# MiniBee.net
KiCad netlist of a schematic drawn in EAGLE
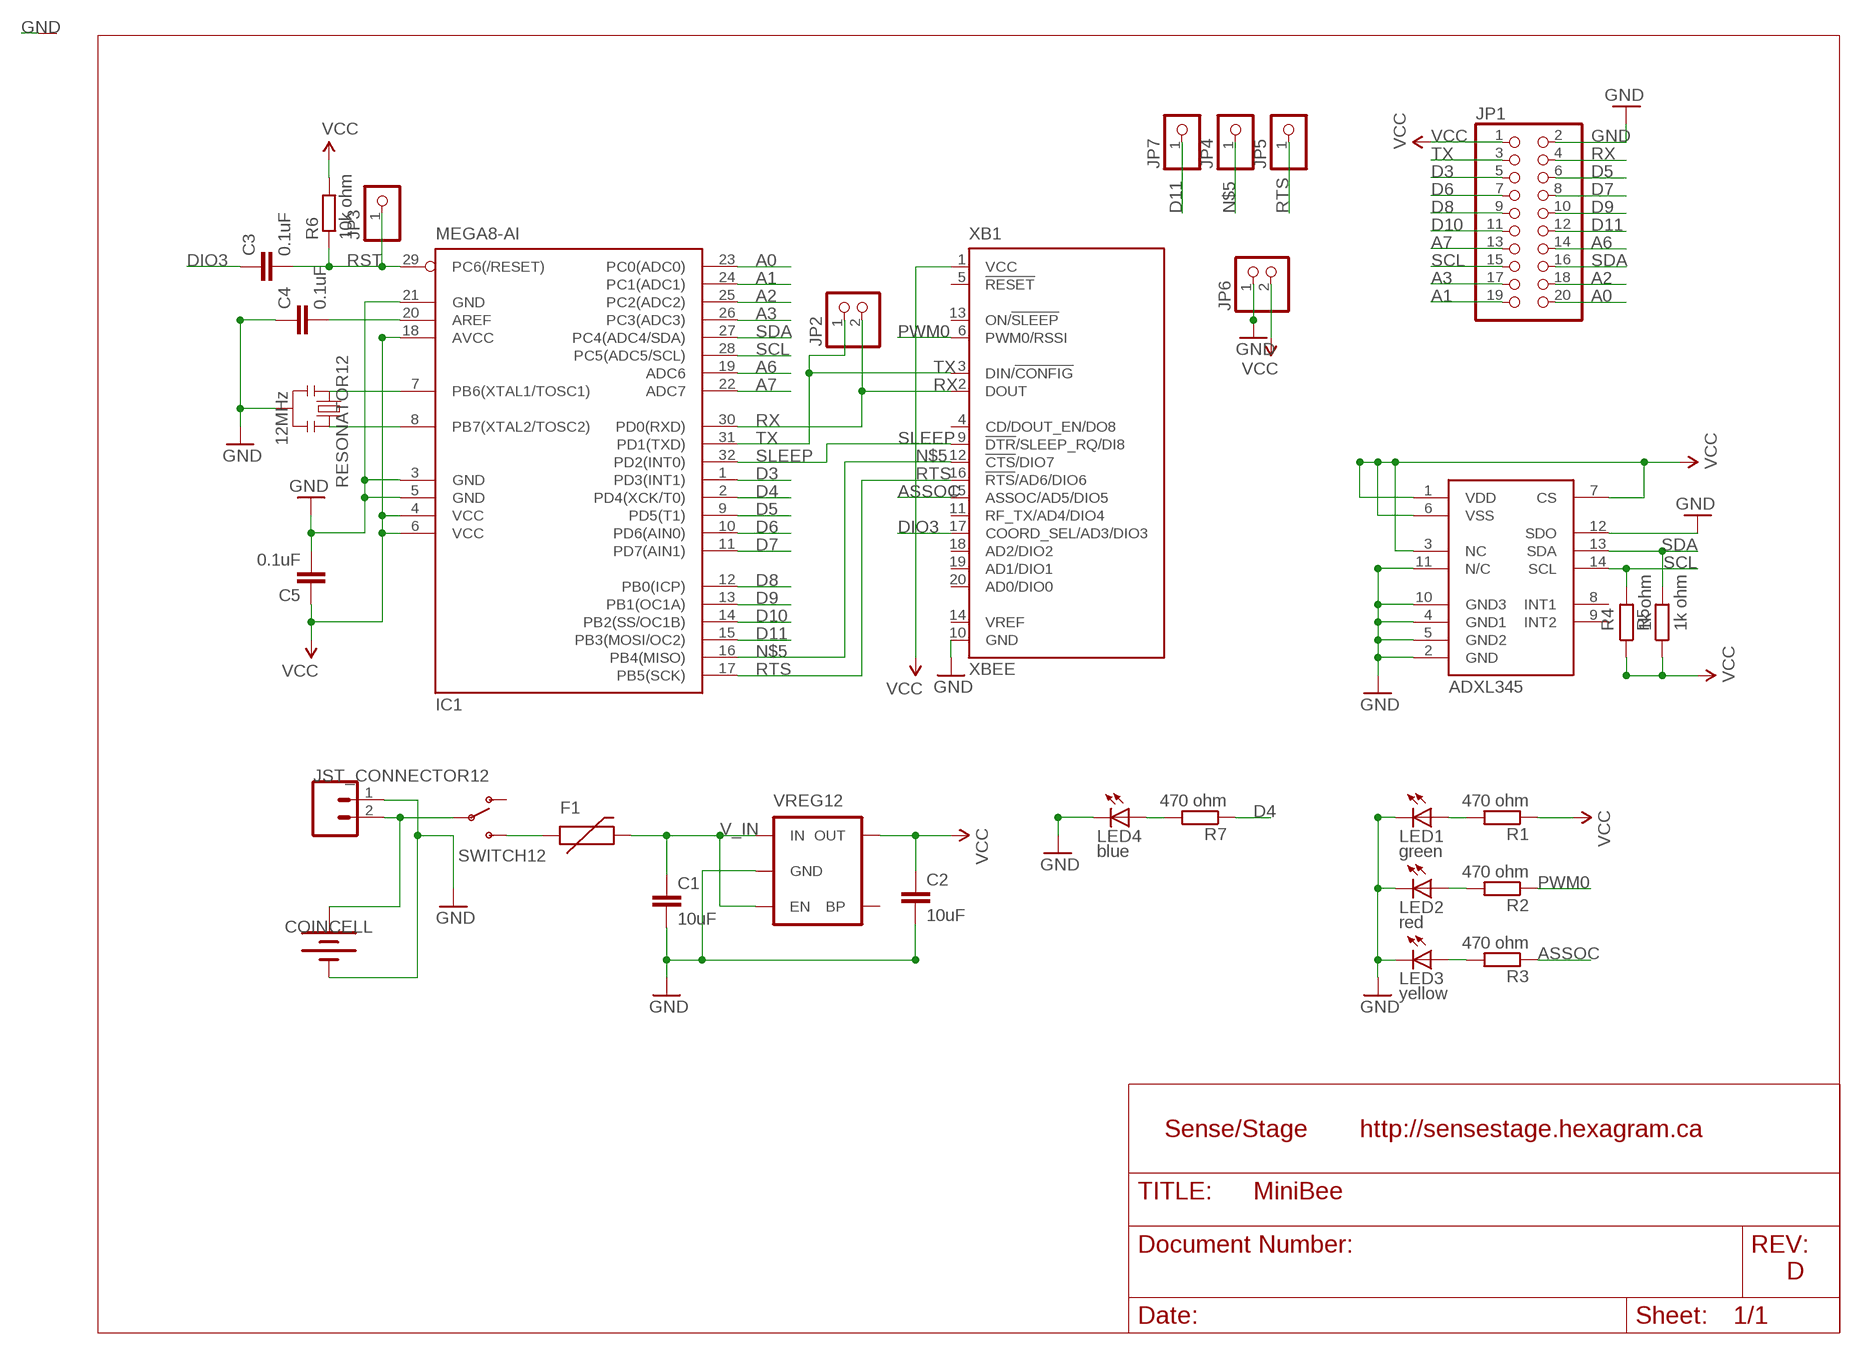
[diagram p0: schematic, sheet 1]

(export (version "E")
  (design (tool "Eeschema 10.0.6"))
  (components
    (comp (ref "C1")
      (value "10uF")
      (footprint "eagle-import:C0805")
      (libsource (lib "eagle-import") (part "C-EUC0805"))
    )
    (comp (ref "C2")
      (value "10uF")
      (footprint "eagle-import:C0805")
      (libsource (lib "eagle-import") (part "C-EUC0805"))
    )
    (comp (ref "C3")
      (value "0.1uF")
      (footprint "eagle-import:C0402")
      (libsource (lib "eagle-import") (part "C-EUC0402"))
    )
    (comp (ref "C4")
      (value "0.1uF")
      (footprint "eagle-import:C0402")
      (libsource (lib "eagle-import") (part "C-EUC0402"))
    )
    (comp (ref "C5")
      (value "0.1uF")
      (footprint "eagle-import:C0402K")
      (libsource (lib "eagle-import") (part "C-EUC0402K"))
    )
    (comp (ref "COINCELL12")
      (value "COINCELL")
      (footprint "eagle-import:KEYSTONE_BATTERY_HOLDER")
      (libsource (lib "eagle-import") (part "KEYSTONE_BATTERY_HOLDER"))
    )
    (comp (ref "F1")
      (value "PTCSMD")
      (footprint "eagle-import:PTC-1206")
      (libsource (lib "eagle-import") (part "PTCSMD"))
    )
    (comp (ref "IC1")
      (value "MEGA8-AI")
      (footprint "eagle-import:TQFP32-08")
      (fields (field (name "MPN") "ATMEGA8-16AU"))
      (libsource (lib "eagle-import") (part "MEGA8-AI"))
    )
    (comp (ref "JP1")
      (value "PINHD-2X10")
      (footprint "eagle-import:2X10")
      (libsource (lib "eagle-import") (part "PINHD-2X10"))
    )
    (comp (ref "JP2")
      (value "PINHD-1X2")
      (footprint "eagle-import:1X02")
      (libsource (lib "eagle-import") (part "PINHD-1X2"))
    )
    (comp (ref "JP3")
      (value "PINHD-1X1")
      (footprint "eagle-import:1X01")
      (libsource (lib "eagle-import") (part "PINHD-1X1"))
    )
    (comp (ref "JP4")
      (value "PINHD-1X1")
      (footprint "eagle-import:1X01")
      (libsource (lib "eagle-import") (part "PINHD-1X1"))
    )
    (comp (ref "JP5")
      (value "PINHD-1X1")
      (footprint "eagle-import:1X01")
      (libsource (lib "eagle-import") (part "PINHD-1X1"))
    )
    (comp (ref "JP6")
      (value "PINHD-1X2")
      (footprint "eagle-import:1X02")
      (libsource (lib "eagle-import") (part "PINHD-1X2"))
    )
    (comp (ref "JP7")
      (value "PINHD-1X1")
      (footprint "eagle-import:1X01")
      (libsource (lib "eagle-import") (part "PINHD-1X1"))
    )
    (comp (ref "JST_CONNECTOR12")
      (value "JST_CONNECTOR")
      (footprint "eagle-import:S2B-PH")
      (libsource (lib "eagle-import") (part "M02-JST-2MM-SMT"))
    )
    (comp (ref "LED1")
      (value "green")
      (footprint "eagle-import:CHIP-LED0603")
      (libsource (lib "eagle-import") (part "LEDCHIP-LED0603"))
    )
    (comp (ref "LED2")
      (value "red")
      (footprint "eagle-import:CHIP-LED0603")
      (libsource (lib "eagle-import") (part "LEDCHIP-LED0603"))
    )
    (comp (ref "LED3")
      (value "yellow")
      (footprint "eagle-import:CHIP-LED0603")
      (libsource (lib "eagle-import") (part "LEDCHIP-LED0603"))
    )
    (comp (ref "LED4")
      (value "blue")
      (footprint "eagle-import:CHIP-LED0603")
      (libsource (lib "eagle-import") (part "LEDCHIP-LED0603"))
    )
    (comp (ref "R1")
      (value "470 ohm")
      (footprint "eagle-import:R0402")
      (libsource (lib "eagle-import") (part "R-EU_R0402"))
    )
    (comp (ref "R2")
      (value "470 ohm")
      (footprint "eagle-import:R0402")
      (libsource (lib "eagle-import") (part "R-EU_R0402"))
    )
    (comp (ref "R3")
      (value "470 ohm")
      (footprint "eagle-import:R0402")
      (libsource (lib "eagle-import") (part "R-EU_R0402"))
    )
    (comp (ref "R4")
      (value "1k ohm")
      (footprint "eagle-import:R0402")
      (libsource (lib "eagle-import") (part "R-EU_R0402"))
    )
    (comp (ref "R5")
      (value "1k ohm")
      (footprint "eagle-import:R0402")
      (libsource (lib "eagle-import") (part "R-EU_R0402"))
    )
    (comp (ref "R6")
      (value "10k ohm")
      (footprint "eagle-import:R0402")
      (libsource (lib "eagle-import") (part "R-EU_R0402"))
    )
    (comp (ref "R7")
      (value "470 ohm")
      (footprint "eagle-import:R0402")
      (libsource (lib "eagle-import") (part "R-EU_R0402"))
    )
    (comp (ref "RESONATOR12")
      (value "12MHz")
      (footprint "eagle-import:RESONATOR-SMD")
      (libsource (lib "eagle-import") (part "RESONATORSMD"))
    )
    (comp (ref "SWITCH12")
      (value "MYSHIT_PCM_SWITCH")
      (footprint "eagle-import:MYSHIT_PCM_SWITCH_RA")
      (libsource (lib "eagle-import") (part "MYSHIT_PCM_SWITCH"))
    )
    (comp (ref "U1")
      (value "ADXL345")
      (footprint "eagle-import:LGA14")
      (libsource (lib "eagle-import") (part "ADXL345"))
    )
    (comp (ref "VP_0")
      (value "VPDEV0")
      (footprint "eagle-import:VPAC0")
      (libsource (lib "eagle-import") (part "VPDEV0"))
    )
    (comp (ref "VREG12")
      (value "V_REG_LDOSMD")
      (footprint "eagle-import:SOT23-5")
      (libsource (lib "eagle-import") (part "V_REG_LDOSMD"))
    )
    (comp (ref "XB1")
      (value "XBEE")
      (footprint "eagle-import:XBEE")
      (fields (field (name "MPN") "XBP24-Z7UIT-004"))
      (libsource (lib "eagle-import") (part "XBEE"))
    )
  )
  (nets
    (net (code "1") (name "/A0") (class "Default")
      (node (ref "IC1") (pin "23") (pinfunction "PC0(ADC0)_23") (pintype "bidirectional"))
      (node (ref "JP1") (pin "20") (pinfunction "20_20") (pintype "passive"))
    )
    (net (code "2") (name "/A1") (class "Default")
      (node (ref "IC1") (pin "24") (pinfunction "PC1(ADC1)_24") (pintype "bidirectional"))
      (node (ref "JP1") (pin "19") (pinfunction "19_19") (pintype "passive"))
    )
    (net (code "3") (name "/A2") (class "Default")
      (node (ref "IC1") (pin "25") (pinfunction "PC2(ADC2)_25") (pintype "bidirectional"))
      (node (ref "JP1") (pin "18") (pinfunction "18_18") (pintype "passive"))
    )
    (net (code "4") (name "/A3") (class "Default")
      (node (ref "IC1") (pin "26") (pinfunction "PC3(ADC3)_26") (pintype "bidirectional"))
      (node (ref "JP1") (pin "17") (pinfunction "17_17") (pintype "passive"))
    )
    (net (code "5") (name "/A6") (class "Default")
      (node (ref "IC1") (pin "19") (pinfunction "ADC6_19") (pintype "bidirectional"))
      (node (ref "JP1") (pin "14") (pinfunction "14_14") (pintype "passive"))
    )
    (net (code "6") (name "/A7") (class "Default")
      (node (ref "IC1") (pin "22") (pinfunction "ADC7_22") (pintype "bidirectional"))
      (node (ref "JP1") (pin "13") (pinfunction "13_13") (pintype "passive"))
    )
    (net (code "7") (name "/ASSOC") (class "Default")
      (node (ref "R3") (pin "1") (pinfunction "1_1") (pintype "passive"))
      (node (ref "XB1") (pin "15") (pinfunction "ASSOC/AD5/DIO5_15") (pintype "bidirectional"))
    )
    (net (code "8") (name "/D3") (class "Default")
      (node (ref "IC1") (pin "1") (pinfunction "PD3(INT1)_1") (pintype "bidirectional"))
      (node (ref "JP1") (pin "5") (pinfunction "5_5") (pintype "passive"))
    )
    (net (code "9") (name "/D4") (class "Default")
      (node (ref "IC1") (pin "2") (pinfunction "PD4(XCK/T0)_2") (pintype "bidirectional"))
      (node (ref "R7") (pin "1") (pinfunction "1_1") (pintype "passive"))
    )
    (net (code "10") (name "/D5") (class "Default")
      (node (ref "IC1") (pin "9") (pinfunction "PD5(T1)_9") (pintype "bidirectional"))
      (node (ref "JP1") (pin "6") (pinfunction "6_6") (pintype "passive"))
    )
    (net (code "11") (name "/D6") (class "Default")
      (node (ref "IC1") (pin "10") (pinfunction "PD6(AIN0)_10") (pintype "bidirectional"))
      (node (ref "JP1") (pin "7") (pinfunction "7_7") (pintype "passive"))
    )
    (net (code "12") (name "/D7") (class "Default")
      (node (ref "IC1") (pin "11") (pinfunction "PD7(AIN1)_11") (pintype "bidirectional"))
      (node (ref "JP1") (pin "8") (pinfunction "8_8") (pintype "passive"))
    )
    (net (code "13") (name "/D8") (class "Default")
      (node (ref "IC1") (pin "12") (pinfunction "PB0(ICP)_12") (pintype "bidirectional"))
      (node (ref "JP1") (pin "9") (pinfunction "9_9") (pintype "passive"))
    )
    (net (code "14") (name "/D9") (class "Default")
      (node (ref "IC1") (pin "13") (pinfunction "PB1(OC1A)_13") (pintype "bidirectional"))
      (node (ref "JP1") (pin "10") (pinfunction "10_10") (pintype "passive"))
    )
    (net (code "15") (name "/D10") (class "Default")
      (node (ref "IC1") (pin "14") (pinfunction "PB2(SS/OC1B)_14") (pintype "bidirectional"))
      (node (ref "JP1") (pin "11") (pinfunction "11_11") (pintype "passive"))
    )
    (net (code "16") (name "/D11") (class "Default")
      (node (ref "IC1") (pin "15") (pinfunction "PB3(MOSI/OC2)_15") (pintype "bidirectional"))
      (node (ref "JP1") (pin "12") (pinfunction "12_12") (pintype "passive"))
      (node (ref "JP7") (pin "1") (pinfunction "1_1") (pintype "passive"))
    )
    (net (code "17") (name "/DIO3") (class "Default")
      (node (ref "C3") (pin "1") (pinfunction "1_1") (pintype "passive"))
      (node (ref "XB1") (pin "17") (pinfunction "COORD_SEL/AD3/DIO3_17") (pintype "bidirectional"))
    )
    (net (code "18") (name "/N$5") (class "Default")
      (node (ref "IC1") (pin "16") (pinfunction "PB4(MISO)_16") (pintype "bidirectional"))
      (node (ref "JP4") (pin "1") (pinfunction "1_1") (pintype "passive"))
      (node (ref "XB1") (pin "12") (pinfunction "~{CTS}/DIO7_12") (pintype "bidirectional"))
    )
    (net (code "19") (name "/PWM0") (class "Default")
      (node (ref "R2") (pin "1") (pinfunction "1_1") (pintype "passive"))
      (node (ref "XB1") (pin "6") (pinfunction "PWM0/RSSI_6") (pintype "output"))
    )
    (net (code "20") (name "/RST") (class "Default")
      (node (ref "C3") (pin "2") (pinfunction "2_2") (pintype "passive"))
      (node (ref "IC1") (pin "29") (pinfunction "PC6(/RESET)_29") (pintype "bidirectional"))
      (node (ref "JP3") (pin "1") (pinfunction "1_1") (pintype "passive"))
      (node (ref "R6") (pin "1") (pinfunction "1_1") (pintype "passive"))
    )
    (net (code "21") (name "/RTS") (class "Default")
      (node (ref "IC1") (pin "17") (pinfunction "PB5(SCK)_17") (pintype "bidirectional"))
      (node (ref "JP5") (pin "1") (pinfunction "1_1") (pintype "passive"))
      (node (ref "XB1") (pin "16") (pinfunction "~{RTS}/AD6/DIO6_16") (pintype "bidirectional"))
    )
    (net (code "22") (name "/RX") (class "Default")
      (node (ref "IC1") (pin "30") (pinfunction "PD0(RXD)_30") (pintype "bidirectional"))
      (node (ref "JP1") (pin "4") (pinfunction "4_4") (pintype "passive"))
      (node (ref "JP2") (pin "2") (pinfunction "2_2") (pintype "passive"))
      (node (ref "XB1") (pin "2") (pinfunction "DOUT_2") (pintype "output"))
    )
    (net (code "23") (name "/SCL") (class "Default")
      (node (ref "IC1") (pin "28") (pinfunction "PC5(ADC5/SCL)_28") (pintype "bidirectional"))
      (node (ref "JP1") (pin "15") (pinfunction "15_15") (pintype "passive"))
      (node (ref "R4") (pin "2") (pinfunction "2_2") (pintype "passive"))
      (node (ref "U1") (pin "14") (pinfunction "SCL_14") (pintype "bidirectional"))
    )
    (net (code "24") (name "/SDA") (class "Default")
      (node (ref "IC1") (pin "27") (pinfunction "PC4(ADC4/SDA)_27") (pintype "bidirectional"))
      (node (ref "JP1") (pin "16") (pinfunction "16_16") (pintype "passive"))
      (node (ref "R5") (pin "2") (pinfunction "2_2") (pintype "passive"))
      (node (ref "U1") (pin "13") (pinfunction "SDA_13") (pintype "bidirectional"))
    )
    (net (code "25") (name "/SLEEP") (class "Default")
      (node (ref "IC1") (pin "32") (pinfunction "PD2(INT0)_32") (pintype "bidirectional"))
      (node (ref "XB1") (pin "9") (pinfunction "~{DTR}/SLEEP_RQ/DI8_9") (pintype "bidirectional"))
    )
    (net (code "26") (name "/TX") (class "Default")
      (node (ref "IC1") (pin "31") (pinfunction "PD1(TXD)_31") (pintype "bidirectional"))
      (node (ref "JP1") (pin "3") (pinfunction "3_3") (pintype "passive"))
      (node (ref "JP2") (pin "1") (pinfunction "1_1") (pintype "passive"))
      (node (ref "XB1") (pin "3") (pinfunction "DIN/~{CONFIG}_3") (pintype "input"))
    )
    (net (code "27") (name "/V_IN") (class "Default")
      (node (ref "C1") (pin "1") (pinfunction "1_1") (pintype "passive"))
      (node (ref "F1") (pin "2") (pinfunction "2_2") (pintype "bidirectional"))
      (node (ref "VREG12") (pin "1") (pinfunction "IN_1") (pintype "input"))
      (node (ref "VREG12") (pin "3") (pinfunction "EN_3") (pintype "input"))
    )
    (net (code "28") (name "GND") (class "Default")
      (node (ref "C1") (pin "2") (pinfunction "2_2") (pintype "passive"))
      (node (ref "C2") (pin "2") (pinfunction "2_2") (pintype "passive"))
      (node (ref "C4") (pin "1") (pinfunction "1_1") (pintype "passive"))
      (node (ref "C5") (pin "2") (pinfunction "2_2") (pintype "passive"))
      (node (ref "COINCELL12") (pin "-") (pinfunction "-_-") (pintype "power_in"))
      (node (ref "IC1") (pin "21") (pinfunction "GND_21") (pintype "power_in"))
      (node (ref "IC1") (pin "3") (pinfunction "GND_3") (pintype "power_in"))
      (node (ref "IC1") (pin "5") (pinfunction "GND_5") (pintype "power_in"))
      (node (ref "JP1") (pin "2") (pinfunction "2_2") (pintype "passive"))
      (node (ref "JP6") (pin "1") (pinfunction "1_1") (pintype "passive"))
      (node (ref "JST_CONNECTOR12") (pin "1") (pinfunction "1_1") (pintype "passive"))
      (node (ref "LED1") (pin "C") (pinfunction "C_C") (pintype "passive"))
      (node (ref "LED2") (pin "C") (pinfunction "C_C") (pintype "passive"))
      (node (ref "LED3") (pin "C") (pinfunction "C_C") (pintype "passive"))
      (node (ref "LED4") (pin "C") (pinfunction "C_C") (pintype "passive"))
      (node (ref "RESONATOR12") (pin "2") (pinfunction "2_2") (pintype "passive"))
      (node (ref "U1") (pin "10") (pinfunction "GND3_10") (pintype "bidirectional"))
      (node (ref "U1") (pin "11") (pinfunction "N/C_11") (pintype "bidirectional"))
      (node (ref "U1") (pin "12") (pinfunction "SDO_12") (pintype "bidirectional"))
      (node (ref "U1") (pin "2") (pinfunction "GND_2") (pintype "bidirectional"))
      (node (ref "U1") (pin "4") (pinfunction "GND1_4") (pintype "bidirectional"))
      (node (ref "U1") (pin "5") (pinfunction "GND2_5") (pintype "bidirectional"))
      (node (ref "VP_0") (pin "VP") (pinfunction "VP_VP") (pintype "passive"))
      (node (ref "VREG12") (pin "2") (pinfunction "GND_2") (pintype "input"))
      (node (ref "XB1") (pin "10") (pinfunction "GND_10") (pintype "power_in"))
    )
    (net (code "29") (name "Net-(IC1-AREF)") (class "Default")
      (node (ref "C4") (pin "2") (pinfunction "2_2") (pintype "passive"))
      (node (ref "IC1") (pin "20") (pinfunction "AREF_20") (pintype "passive"))
    )
    (net (code "30") (name "Net-(IC1-PB6(XTAL1{slash}TOSC1))") (class "Default")
      (node (ref "IC1") (pin "7") (pinfunction "PB6(XTAL1/TOSC1)_7") (pintype "bidirectional"))
      (node (ref "RESONATOR12") (pin "1") (pinfunction "1_1") (pintype "passive"))
    )
    (net (code "31") (name "Net-(IC1-PB7(XTAL2{slash}TOSC2))") (class "Default")
      (node (ref "IC1") (pin "8") (pinfunction "PB7(XTAL2/TOSC2)_8") (pintype "bidirectional"))
      (node (ref "RESONATOR12") (pin "3") (pinfunction "3_3") (pintype "passive"))
    )
    (net (code "32") (name "Net-(LED1-PadA)") (class "Default")
      (node (ref "LED1") (pin "A") (pinfunction "A_A") (pintype "passive"))
      (node (ref "R1") (pin "2") (pinfunction "2_2") (pintype "passive"))
    )
    (net (code "33") (name "Net-(LED2-PadA)") (class "Default")
      (node (ref "LED2") (pin "A") (pinfunction "A_A") (pintype "passive"))
      (node (ref "R2") (pin "2") (pinfunction "2_2") (pintype "passive"))
    )
    (net (code "34") (name "Net-(LED3-PadA)") (class "Default")
      (node (ref "LED3") (pin "A") (pinfunction "A_A") (pintype "passive"))
      (node (ref "R3") (pin "2") (pinfunction "2_2") (pintype "passive"))
    )
    (net (code "35") (name "Net-(LED4-PadA)") (class "Default")
      (node (ref "LED4") (pin "A") (pinfunction "A_A") (pintype "passive"))
      (node (ref "R7") (pin "2") (pinfunction "2_2") (pintype "passive"))
    )
    (net (code "36") (name "Net-(SWITCH12-P)") (class "Default")
      (node (ref "COINCELL12") (pin "+") (pinfunction "+_+") (pintype "power_in"))
      (node (ref "JST_CONNECTOR12") (pin "2") (pinfunction "2_2") (pintype "passive"))
      (node (ref "SWITCH12") (pin "2") (pinfunction "P_2") (pintype "passive"))
    )
    (net (code "37") (name "Net-(SWITCH12-S)") (class "Default")
      (node (ref "F1") (pin "1") (pinfunction "1_1") (pintype "bidirectional"))
      (node (ref "SWITCH12") (pin "3") (pinfunction "S_3") (pintype "passive"))
    )
    (net (code "38") (name "VCC") (class "Default")
      (node (ref "C2") (pin "1") (pinfunction "1_1") (pintype "passive"))
      (node (ref "C5") (pin "1") (pinfunction "1_1") (pintype "passive"))
      (node (ref "IC1") (pin "18") (pinfunction "AVCC_18") (pintype "power_in"))
      (node (ref "IC1") (pin "4") (pinfunction "VCC_4") (pintype "power_in"))
      (node (ref "IC1") (pin "6") (pinfunction "VCC_6") (pintype "power_in"))
      (node (ref "JP1") (pin "1") (pinfunction "1_1") (pintype "passive"))
      (node (ref "JP6") (pin "2") (pinfunction "2_2") (pintype "passive"))
      (node (ref "R1") (pin "1") (pinfunction "1_1") (pintype "passive"))
      (node (ref "R4") (pin "1") (pinfunction "1_1") (pintype "passive"))
      (node (ref "R5") (pin "1") (pinfunction "1_1") (pintype "passive"))
      (node (ref "R6") (pin "2") (pinfunction "2_2") (pintype "passive"))
      (node (ref "U1") (pin "1") (pinfunction "VDD_1") (pintype "bidirectional"))
      (node (ref "U1") (pin "3") (pinfunction "NC_3") (pintype "bidirectional"))
      (node (ref "U1") (pin "6") (pinfunction "VSS_6") (pintype "bidirectional"))
      (node (ref "U1") (pin "7") (pinfunction "CS_7") (pintype "bidirectional"))
      (node (ref "VREG12") (pin "5") (pinfunction "OUT_5") (pintype "passive"))
      (node (ref "XB1") (pin "1") (pinfunction "VCC_1") (pintype "power_in"))
    )
    (net (code "39") (name "unconnected-(SWITCH12-O-Pad1)") (class "Default")
      (node (ref "SWITCH12") (pin "1") (pinfunction "O_1") (pintype "passive"))
    )
    (net (code "40") (name "unconnected-(U1-INT1-Pad8)") (class "Default")
      (node (ref "U1") (pin "8") (pinfunction "INT1_8") (pintype "bidirectional"))
    )
    (net (code "41") (name "unconnected-(U1-INT2-Pad9)") (class "Default")
      (node (ref "U1") (pin "9") (pinfunction "INT2_9") (pintype "bidirectional"))
    )
    (net (code "42") (name "unconnected-(VREG12-BP-Pad4)") (class "Default")
      (node (ref "VREG12") (pin "4") (pinfunction "BP_4") (pintype "input"))
    )
    (net (code "43") (name "unconnected-(XB1-AD0{slash}DIO0-Pad20)") (class "Default")
      (node (ref "XB1") (pin "20") (pinfunction "AD0/DIO0_20") (pintype "bidirectional"))
    )
    (net (code "44") (name "unconnected-(XB1-AD1{slash}DIO1-Pad19)") (class "Default")
      (node (ref "XB1") (pin "19") (pinfunction "AD1/DIO1_19") (pintype "bidirectional"))
    )
    (net (code "45") (name "unconnected-(XB1-AD2{slash}DIO2-Pad18)") (class "Default")
      (node (ref "XB1") (pin "18") (pinfunction "AD2/DIO2_18") (pintype "bidirectional"))
    )
    (net (code "46") (name "unconnected-(XB1-CD{slash}DOUT_EN{slash}DO8-Pad4)") (class "Default")
      (node (ref "XB1") (pin "4") (pinfunction "CD/DOUT_EN/DO8_4") (pintype "output"))
    )
    (net (code "47") (name "unconnected-(XB1-ON{slash}~{SLEEP}-Pad13)") (class "Default")
      (node (ref "XB1") (pin "13") (pinfunction "ON/~{SLEEP}_13") (pintype "output"))
    )
    (net (code "48") (name "unconnected-(XB1-RF_TX{slash}AD4{slash}DIO4-Pad11)") (class "Default")
      (node (ref "XB1") (pin "11") (pinfunction "RF_TX/AD4/DIO4_11") (pintype "bidirectional"))
    )
    (net (code "49") (name "unconnected-(XB1-VREF-Pad14)") (class "Default")
      (node (ref "XB1") (pin "14") (pinfunction "VREF_14") (pintype "input"))
    )
    (net (code "50") (name "unconnected-(XB1-~{RESET}-Pad5)") (class "Default")
      (node (ref "XB1") (pin "5") (pinfunction "~{RESET}_5") (pintype "input"))
    )
  )
)
